# CAN.net
KiCad netlist of a schematic drawn in Altium Designer
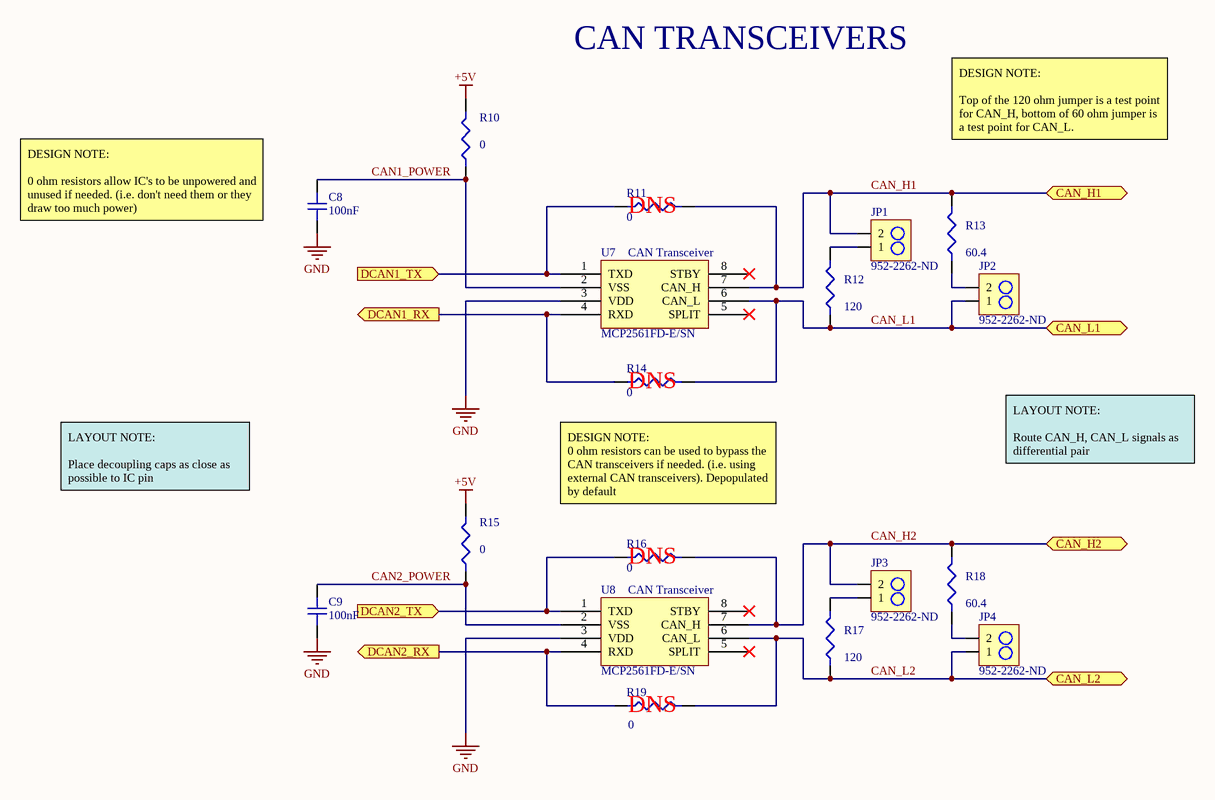
[diagram p0: CAN.SchDoc]

(export (version "E")
  (design (tool "Eeschema 10.0.6"))
  (components
    (comp (ref "C8")
      (value "100nF")
      (footprint "PHANTOM_FOOTPRINTS:C0805")
      (description "MLCC SMD CAP 100nF 10Volts U2J 5%")
      (fields
        (field (name "MANUFACTURER") "Murata")
        (field (name "MANUFACTURER PART NUMBER") "GRM21B7U1A104JA01L")
      )
      (libsource (lib "PHANTOM_LIBRARY") (part "GRM21B7U1A104JA01L"))
    )
    (comp (ref "C9")
      (value "100nF")
      (footprint "PHANTOM_FOOTPRINTS:C0805")
      (description "MLCC SMD CAP 100nF 10Volts U2J 5%")
      (fields
        (field (name "MANUFACTURER") "Murata")
        (field (name "MANUFACTURER PART NUMBER") "GRM21B7U1A104JA01L")
      )
      (libsource (lib "PHANTOM_LIBRARY") (part "GRM21B7U1A104JA01L"))
    )
    (comp (ref "JP1")
      (value "952-2262-ND")
      (footprint "2PIN_HEADER")
      (description "Headers & Wire Housings 02 SIL VERTICAL PIN HEADER TIN")
      (fields (field (name "MANUFACTURER") "Harwin") (field (name "MANUFACTURER PART NUMBER") "M20-9990246"))
      (libsource (lib "PHANTOM_LIBRARY") (part "M20-9990246"))
    )
    (comp (ref "JP2")
      (value "952-2262-ND")
      (footprint "2PIN_HEADER")
      (description "Headers & Wire Housings 02 SIL VERTICAL PIN HEADER TIN")
      (fields (field (name "MANUFACTURER") "Harwin") (field (name "MANUFACTURER PART NUMBER") "M20-9990246"))
      (libsource (lib "PHANTOM_LIBRARY") (part "M20-9990246"))
    )
    (comp (ref "JP3")
      (value "952-2262-ND")
      (footprint "2PIN_HEADER")
      (description "Headers & Wire Housings 02 SIL VERTICAL PIN HEADER TIN")
      (fields (field (name "MANUFACTURER") "Harwin") (field (name "MANUFACTURER PART NUMBER") "M20-9990246"))
      (libsource (lib "PHANTOM_LIBRARY") (part "M20-9990246"))
    )
    (comp (ref "JP4")
      (value "952-2262-ND")
      (footprint "2PIN_HEADER")
      (description "Headers & Wire Housings 02 SIL VERTICAL PIN HEADER TIN")
      (fields (field (name "MANUFACTURER") "Harwin") (field (name "MANUFACTURER PART NUMBER") "M20-9990246"))
      (libsource (lib "PHANTOM_LIBRARY") (part "M20-9990246"))
    )
    (comp (ref "R10")
      (value "0")
      (footprint "R0805")
      (description "RES SMD 0 OHM 1/8W 0805")
      (fields
        (field (name "MANUFACTURER") "Yageo")
        (field (name "MANUFACTURER PART NUMBER") "RC0805JR-070RL")
      )
      (libsource (lib "PHANTOM_LIBRARY") (part "RC0805JR-070RL"))
    )
    (comp (ref "R11")
      (value "0")
      (footprint "R0805")
      (description "RES SMD 0 OHM 1/8W 0805")
      (fields
        (field (name "MANUFACTURER") "Yageo")
        (field (name "MANUFACTURER PART NUMBER") "RC0805JR-070RL")
      )
      (libsource (lib "PHANTOM_LIBRARY") (part "RC0805JR-070RL"))
    )
    (comp (ref "R12")
      (value "120")
      (footprint "R0805")
      (description "RES SMD 120 OHM 1% 1/8W 0805")
      (fields
        (field (name "MANUFACTURER") "Yageo")
        (field (name "MANUFACTURER PART NUMBER") "RC0805FR-07120RL")
      )
      (libsource (lib "PHANTOM_LIBRARY") (part "RC0805FR-07120RL"))
    )
    (comp (ref "R13")
      (value "60.4")
      (footprint "R0805")
      (description "RES SMD 60.4 OHM 1% 1/8W 0805")
      (fields
        (field (name "MANUFACTURER") "Yageo")
        (field (name "MANUFACTURER PART NUMBER") "RC0805FR-0760R4L")
      )
      (libsource (lib "PHANTOM_LIBRARY") (part "RC0805FR-0760R4L"))
    )
    (comp (ref "R14")
      (value "0")
      (footprint "R0805")
      (description "RES SMD 0 OHM 1/8W 0805")
      (fields
        (field (name "MANUFACTURER") "Yageo")
        (field (name "MANUFACTURER PART NUMBER") "RC0805JR-070RL")
      )
      (libsource (lib "PHANTOM_LIBRARY") (part "RC0805JR-070RL"))
    )
    (comp (ref "R15")
      (value "0")
      (footprint "R0805")
      (description "RES SMD 0 OHM 1/8W 0805")
      (fields
        (field (name "MANUFACTURER") "Yageo")
        (field (name "MANUFACTURER PART NUMBER") "RC0805JR-070RL")
      )
      (libsource (lib "PHANTOM_LIBRARY") (part "RC0805JR-070RL"))
    )
    (comp (ref "R16")
      (value "0")
      (footprint "R0805")
      (description "RES SMD 0 OHM 1/8W 0805")
      (fields
        (field (name "MANUFACTURER") "Yageo")
        (field (name "MANUFACTURER PART NUMBER") "RC0805JR-070RL")
      )
      (libsource (lib "PHANTOM_LIBRARY") (part "RC0805JR-070RL"))
    )
    (comp (ref "R17")
      (value "120")
      (footprint "R0805")
      (description "RES SMD 120 OHM 1% 1/8W 0805")
      (fields
        (field (name "MANUFACTURER") "Yageo")
        (field (name "MANUFACTURER PART NUMBER") "RC0805FR-07120RL")
      )
      (libsource (lib "PHANTOM_LIBRARY") (part "RC0805FR-07120RL"))
    )
    (comp (ref "R18")
      (value "60.4")
      (footprint "R0805")
      (description "RES SMD 60.4 OHM 1% 1/8W 0805")
      (fields
        (field (name "MANUFACTURER") "Yageo")
        (field (name "MANUFACTURER PART NUMBER") "RC0805FR-0760R4L")
      )
      (libsource (lib "PHANTOM_LIBRARY") (part "RC0805FR-0760R4L"))
    )
    (comp (ref "R19")
      (value "0")
      (footprint "R0805")
      (description "RES SMD 0 OHM 1/8W 0805")
      (fields
        (field (name "MANUFACTURER") "Yageo")
        (field (name "MANUFACTURER PART NUMBER") "RC0805JR-070RL")
      )
      (libsource (lib "PHANTOM_LIBRARY") (part "RC0805JR-070RL"))
    )
    (comp (ref "U7")
      (value "MCP2561FD-E/SN")
      (footprint "8-SOIC_MCP2561")
      (description "MICROCHIP         MCP2561FD-E/SN            CAN Bus, Transceiver, CAN, 1, 1, 4.5 V, 5.5 V, SOIC")
      (fields (field (name "MANUFACTURER") "Microchip"))
      (libsource (lib "PHANTOM_LIBRARY") (part "MCP2561FD-E/SN"))
    )
    (comp (ref "U8")
      (value "MCP2561FD-E/SN")
      (footprint "8-SOIC_MCP2561")
      (description "MICROCHIP         MCP2561FD-E/SN            CAN Bus, Transceiver, CAN, 1, 1, 4.5 V, 5.5 V, SOIC")
      (fields (field (name "MANUFACTURER") "Microchip"))
      (libsource (lib "PHANTOM_LIBRARY") (part "MCP2561FD-E/SN"))
    )
  )
  (nets
    (net (code "1") (name "+5V") (class "Default")
      (node (ref "R10") (pin "2") (pinfunction "2_2") (pintype "passive"))
      (node (ref "R15") (pin "2") (pinfunction "2_2") (pintype "passive"))
    )
    (net (code "2") (name "/CAN1_POWER") (class "Default")
      (node (ref "C8") (pin "2") (pinfunction "2_2") (pintype "passive"))
      (node (ref "R10") (pin "1") (pinfunction "1_1") (pintype "passive"))
      (node (ref "U7") (pin "2") (pinfunction "VSS_2") (pintype "passive"))
    )
    (net (code "3") (name "/CAN2_POWER") (class "Default")
      (node (ref "C9") (pin "2") (pinfunction "2_2") (pintype "passive"))
      (node (ref "R15") (pin "1") (pinfunction "1_1") (pintype "passive"))
      (node (ref "U8") (pin "2") (pinfunction "VSS_2") (pintype "passive"))
    )
    (net (code "4") (name "/CAN_H1") (class "Default")
      (node (ref "JP1") (pin "2") (pinfunction "2_2") (pintype "passive"))
      (node (ref "R11") (pin "2") (pinfunction "2_2") (pintype "passive"))
      (node (ref "R13") (pin "2") (pinfunction "2_2") (pintype "passive"))
      (node (ref "U7") (pin "7") (pinfunction "CAN_H_7") (pintype "passive"))
    )
    (net (code "5") (name "/CAN_H2") (class "Default")
      (node (ref "JP3") (pin "2") (pinfunction "2_2") (pintype "passive"))
      (node (ref "R16") (pin "2") (pinfunction "2_2") (pintype "passive"))
      (node (ref "R18") (pin "2") (pinfunction "2_2") (pintype "passive"))
      (node (ref "U8") (pin "7") (pinfunction "CAN_H_7") (pintype "passive"))
    )
    (net (code "6") (name "/CAN_L1") (class "Default")
      (node (ref "JP2") (pin "1") (pinfunction "1_1") (pintype "passive"))
      (node (ref "R12") (pin "1") (pinfunction "1_1") (pintype "passive"))
      (node (ref "R14") (pin "2") (pinfunction "2_2") (pintype "passive"))
      (node (ref "U7") (pin "6") (pinfunction "CAN_L_6") (pintype "passive"))
    )
    (net (code "7") (name "/CAN_L2") (class "Default")
      (node (ref "JP4") (pin "1") (pinfunction "1_1") (pintype "passive"))
      (node (ref "R17") (pin "1") (pinfunction "1_1") (pintype "passive"))
      (node (ref "R19") (pin "2") (pinfunction "2_2") (pintype "passive"))
      (node (ref "U8") (pin "6") (pinfunction "CAN_L_6") (pintype "passive"))
    )
    (net (code "8") (name "/DCAN1_RX") (class "Default")
      (node (ref "R14") (pin "1") (pinfunction "1_1") (pintype "passive"))
      (node (ref "U7") (pin "4") (pinfunction "RXD_4") (pintype "passive"))
    )
    (net (code "9") (name "/DCAN1_TX") (class "Default")
      (node (ref "R11") (pin "1") (pinfunction "1_1") (pintype "passive"))
      (node (ref "U7") (pin "1") (pinfunction "TXD_1") (pintype "passive"))
    )
    (net (code "10") (name "/DCAN2_RX") (class "Default")
      (node (ref "R19") (pin "1") (pinfunction "1_1") (pintype "passive"))
      (node (ref "U8") (pin "4") (pinfunction "RXD_4") (pintype "passive"))
    )
    (net (code "11") (name "/DCAN2_TX") (class "Default")
      (node (ref "R16") (pin "1") (pinfunction "1_1") (pintype "passive"))
      (node (ref "U8") (pin "1") (pinfunction "TXD_1") (pintype "passive"))
    )
    (net (code "12") (name "GND") (class "Default")
      (node (ref "C8") (pin "1") (pinfunction "1_1") (pintype "passive"))
      (node (ref "C9") (pin "1") (pinfunction "1_1") (pintype "passive"))
      (node (ref "U7") (pin "3") (pinfunction "VDD_3") (pintype "passive"))
      (node (ref "U8") (pin "3") (pinfunction "VDD_3") (pintype "passive"))
    )
    (net (code "13") (name "Net-(JP1-Pad1)") (class "Default")
      (node (ref "JP1") (pin "1") (pinfunction "1_1") (pintype "passive"))
      (node (ref "R12") (pin "2") (pinfunction "2_2") (pintype "passive"))
    )
    (net (code "14") (name "Net-(JP2-Pad2)") (class "Default")
      (node (ref "JP2") (pin "2") (pinfunction "2_2") (pintype "passive"))
      (node (ref "R13") (pin "1") (pinfunction "1_1") (pintype "passive"))
    )
    (net (code "15") (name "Net-(JP3-Pad1)") (class "Default")
      (node (ref "JP3") (pin "1") (pinfunction "1_1") (pintype "passive"))
      (node (ref "R17") (pin "2") (pinfunction "2_2") (pintype "passive"))
    )
    (net (code "16") (name "Net-(JP4-Pad2)") (class "Default")
      (node (ref "JP4") (pin "2") (pinfunction "2_2") (pintype "passive"))
      (node (ref "R18") (pin "1") (pinfunction "1_1") (pintype "passive"))
    )
    (net (code "17") (name "unconnected-(U7-SPLIT-Pad5)") (class "Default")
      (node (ref "U7") (pin "5") (pinfunction "SPLIT_5") (pintype "passive+no_connect"))
    )
    (net (code "18") (name "unconnected-(U7-STBY-Pad8)") (class "Default")
      (node (ref "U7") (pin "8") (pinfunction "STBY_8") (pintype "passive+no_connect"))
    )
    (net (code "19") (name "unconnected-(U8-SPLIT-Pad5)") (class "Default")
      (node (ref "U8") (pin "5") (pinfunction "SPLIT_5") (pintype "passive+no_connect"))
    )
    (net (code "20") (name "unconnected-(U8-STBY-Pad8)") (class "Default")
      (node (ref "U8") (pin "8") (pinfunction "STBY_8") (pintype "passive+no_connect"))
    )
  )
)
